# rocker.net
KiCad netlist of a schematic drawn in EasyEDA Pro
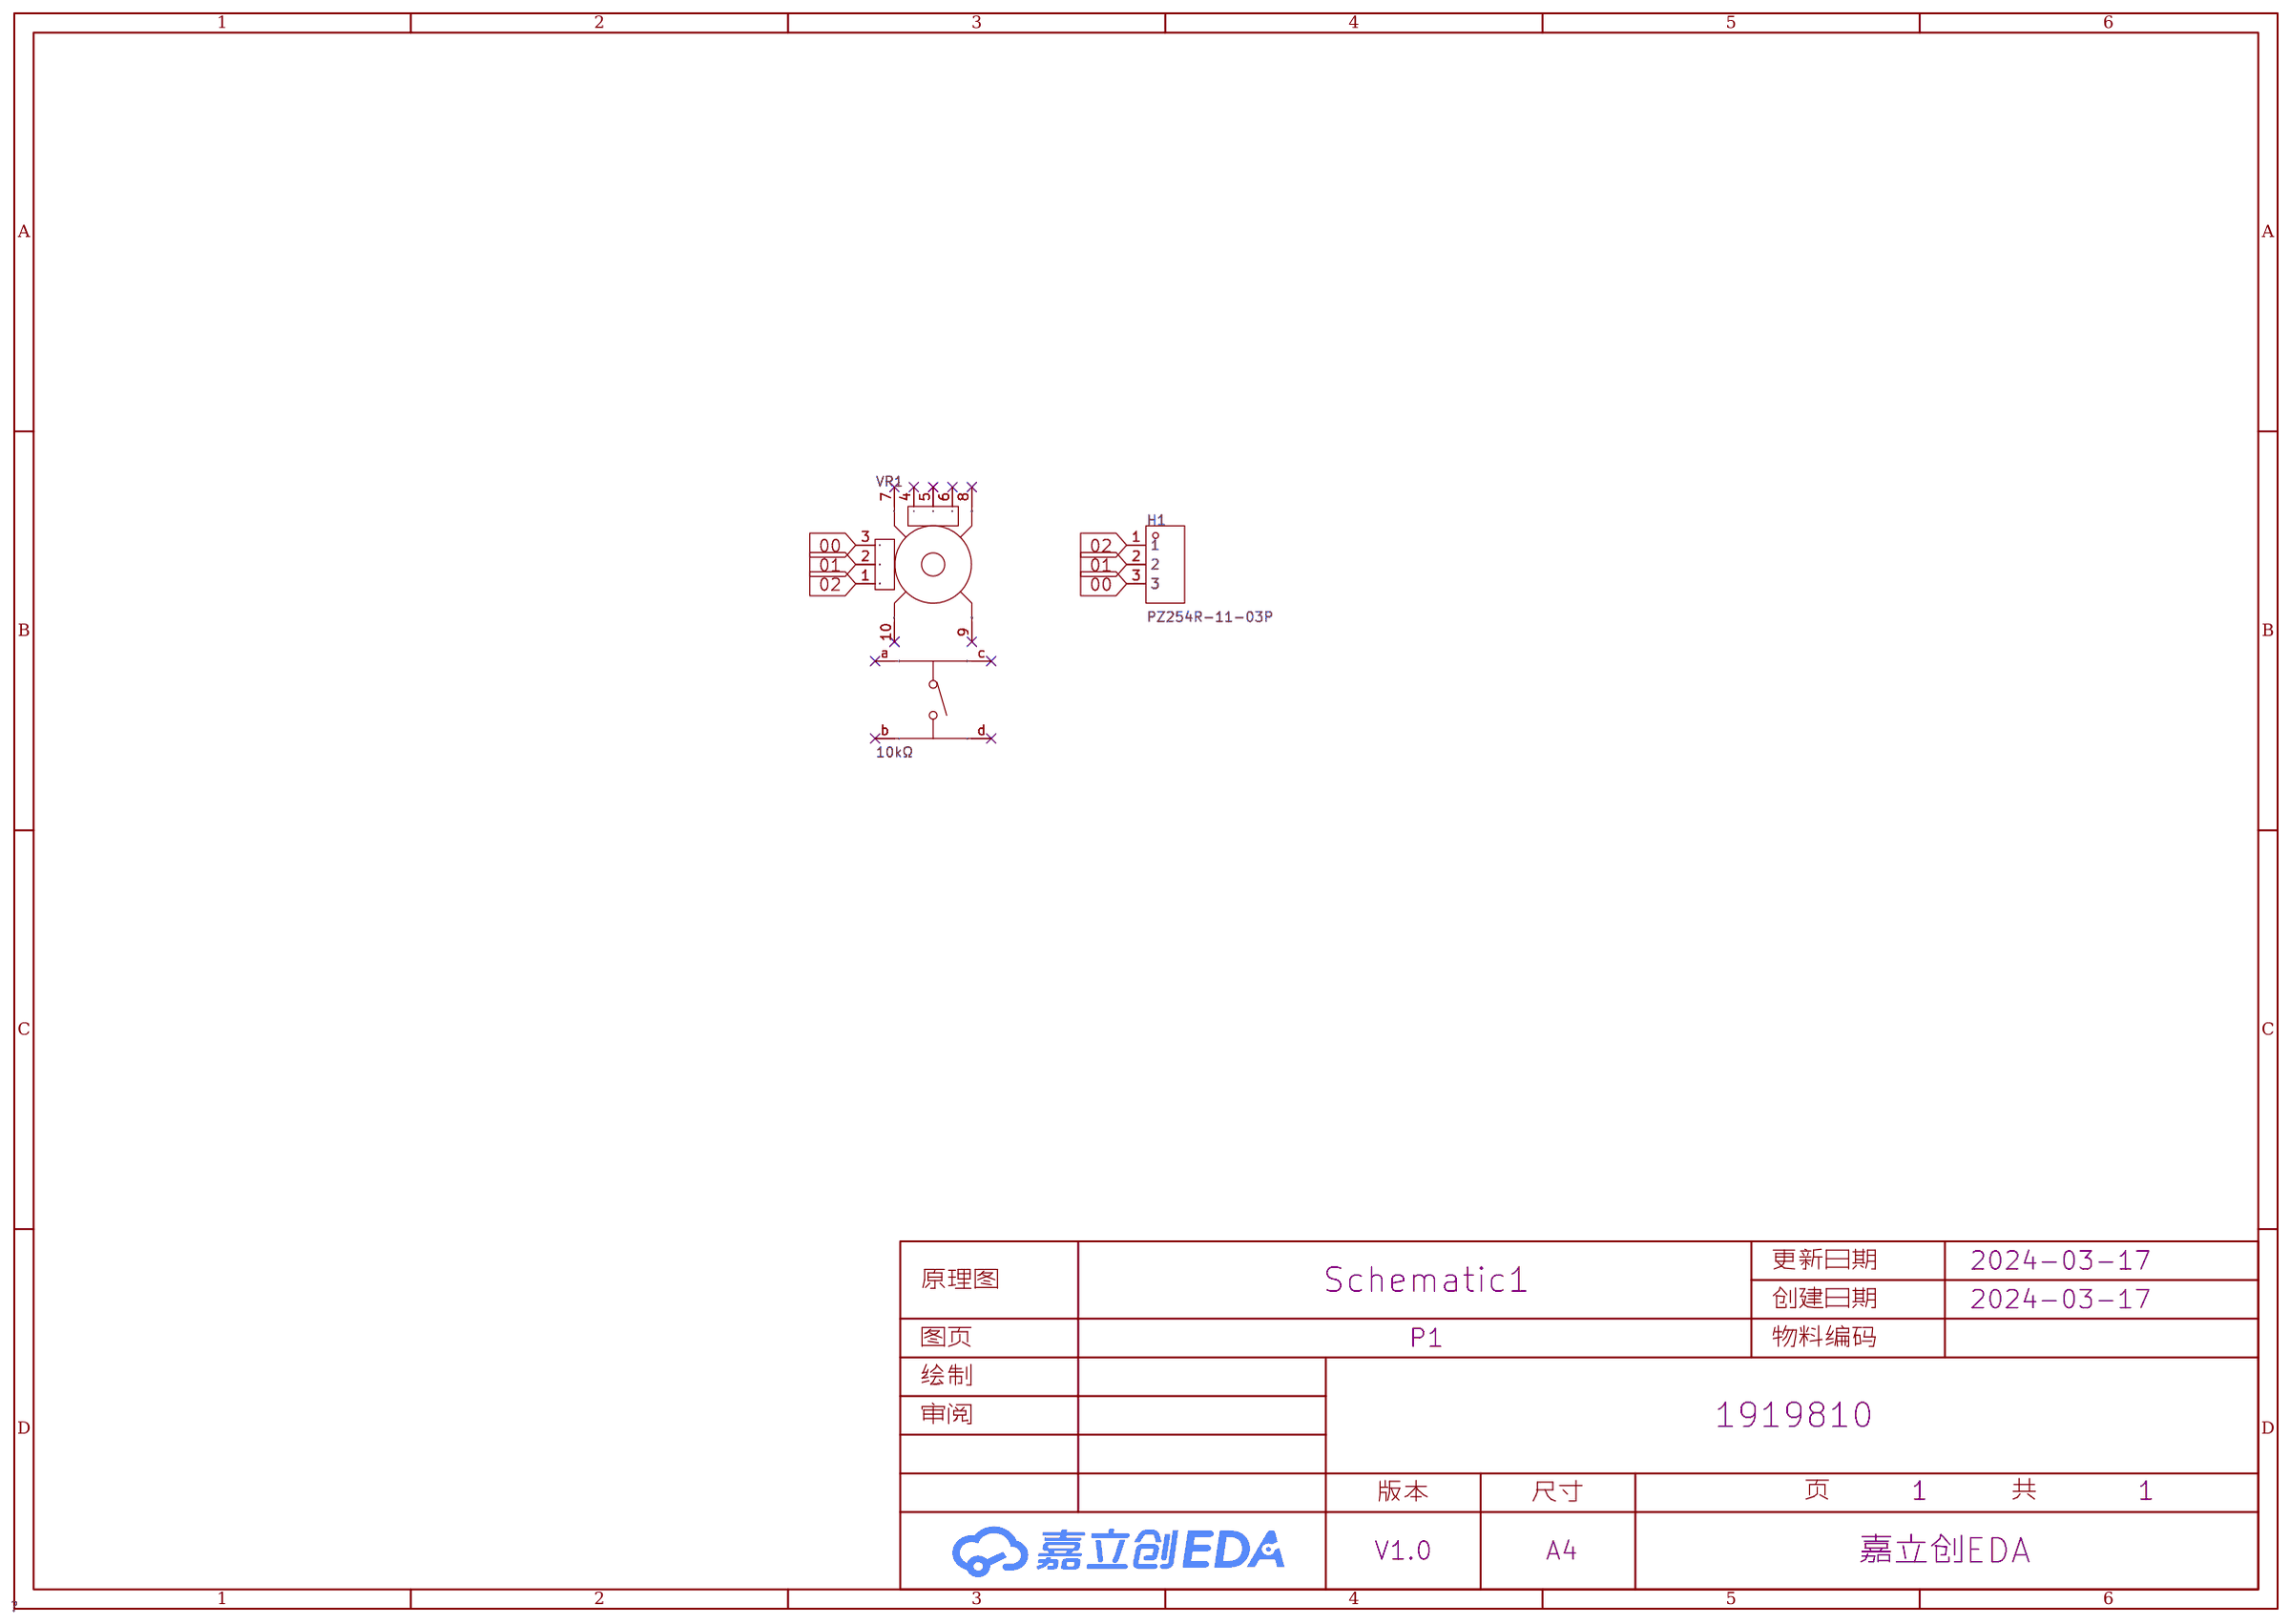
[diagram p0: schematic sheet]

(export (version "E")
  (design (tool "Eeschema 10.0.6"))
  (components
    (comp (ref "H1")
      (value "PZ254R-11-03P")
      (footprint "easyedapro:HDR-TH_3P-P2.54-H-M-W10.4")
      (fields (field (name "Manufacturer") "XFCN(兴飞)"))
      (libsource (lib "easyedapro") (part "PZ254R-11-03P"))
    )
    (comp (ref "VR1")
      (value "10kΩ")
      (footprint "easyedapro:SW-TH_RKJXV1224005")
      (description "阻值:10kΩ;精度:±5%;功率:125mW;")
      (fields
        (field (name "Manufacturer Part") "RKJXV122400R")
        (field (name "Manufacturer") "ALPSALPINE(阿尔卑斯阿尔派)")
      )
      (libsource (lib "easyedapro") (part "RKJXV122400R"))
    )
  )
  (nets
    (net (code "1") (name "00") (class "Default")
      (node (ref "H1") (pin "3") (pinfunction "3_3") (pintype "unspecified"))
      (node (ref "VR1") (pin "3") (pinfunction "A_3") (pintype "unspecified"))
    )
    (net (code "2") (name "01") (class "Default")
      (node (ref "H1") (pin "2") (pinfunction "2_2") (pintype "unspecified"))
      (node (ref "VR1") (pin "2") (pinfunction "DTA_2") (pintype "unspecified"))
    )
    (net (code "3") (name "02") (class "Default")
      (node (ref "H1") (pin "1") (pinfunction "1_1") (pintype "unspecified"))
      (node (ref "VR1") (pin "1") (pinfunction "B_1") (pintype "unspecified"))
    )
    (net (code "4") (name "unconnected-(VR1-A-Pad4)") (class "Default")
      (node (ref "VR1") (pin "4") (pinfunction "A_4") (pintype "unspecified+no_connect"))
    )
    (net (code "5") (name "unconnected-(VR1-B-Pad6)") (class "Default")
      (node (ref "VR1") (pin "6") (pinfunction "B_6") (pintype "unspecified+no_connect"))
    )
    (net (code "6") (name "unconnected-(VR1-DTA-Pad5)") (class "Default")
      (node (ref "VR1") (pin "5") (pinfunction "DTA_5") (pintype "unspecified+no_connect"))
    )
    (net (code "7") (name "unconnected-(VR1-GND-Pad7)") (class "Default")
      (node (ref "VR1") (pin "7") (pinfunction "GND_7") (pintype "unspecified+no_connect"))
    )
    (net (code "8") (name "unconnected-(VR1-GND-Pad8)") (class "Default")
      (node (ref "VR1") (pin "8") (pinfunction "GND_8") (pintype "unspecified+no_connect"))
    )
    (net (code "9") (name "unconnected-(VR1-GND-Pad9)") (class "Default")
      (node (ref "VR1") (pin "9") (pinfunction "GND_9") (pintype "unspecified+no_connect"))
    )
    (net (code "10") (name "unconnected-(VR1-GND-Pad10)") (class "Default")
      (node (ref "VR1") (pin "10") (pinfunction "GND_10") (pintype "unspecified+no_connect"))
    )
    (net (code "11") (name "unconnected-(VR1-Pada)") (class "Default")
      (node (ref "VR1") (pin "a") (pinfunction "a_a") (pintype "unspecified+no_connect"))
    )
    (net (code "12") (name "unconnected-(VR1-Padb)") (class "Default")
      (node (ref "VR1") (pin "b") (pinfunction "b_b") (pintype "unspecified+no_connect"))
    )
    (net (code "13") (name "unconnected-(VR1-Padc)") (class "Default")
      (node (ref "VR1") (pin "c") (pinfunction "c_c") (pintype "unspecified+no_connect"))
    )
    (net (code "14") (name "unconnected-(VR1-Padd)") (class "Default")
      (node (ref "VR1") (pin "d") (pinfunction "d_d") (pintype "unspecified+no_connect"))
    )
  )
)
